# Power.net
KiCad netlist of a schematic drawn in Altium Designer
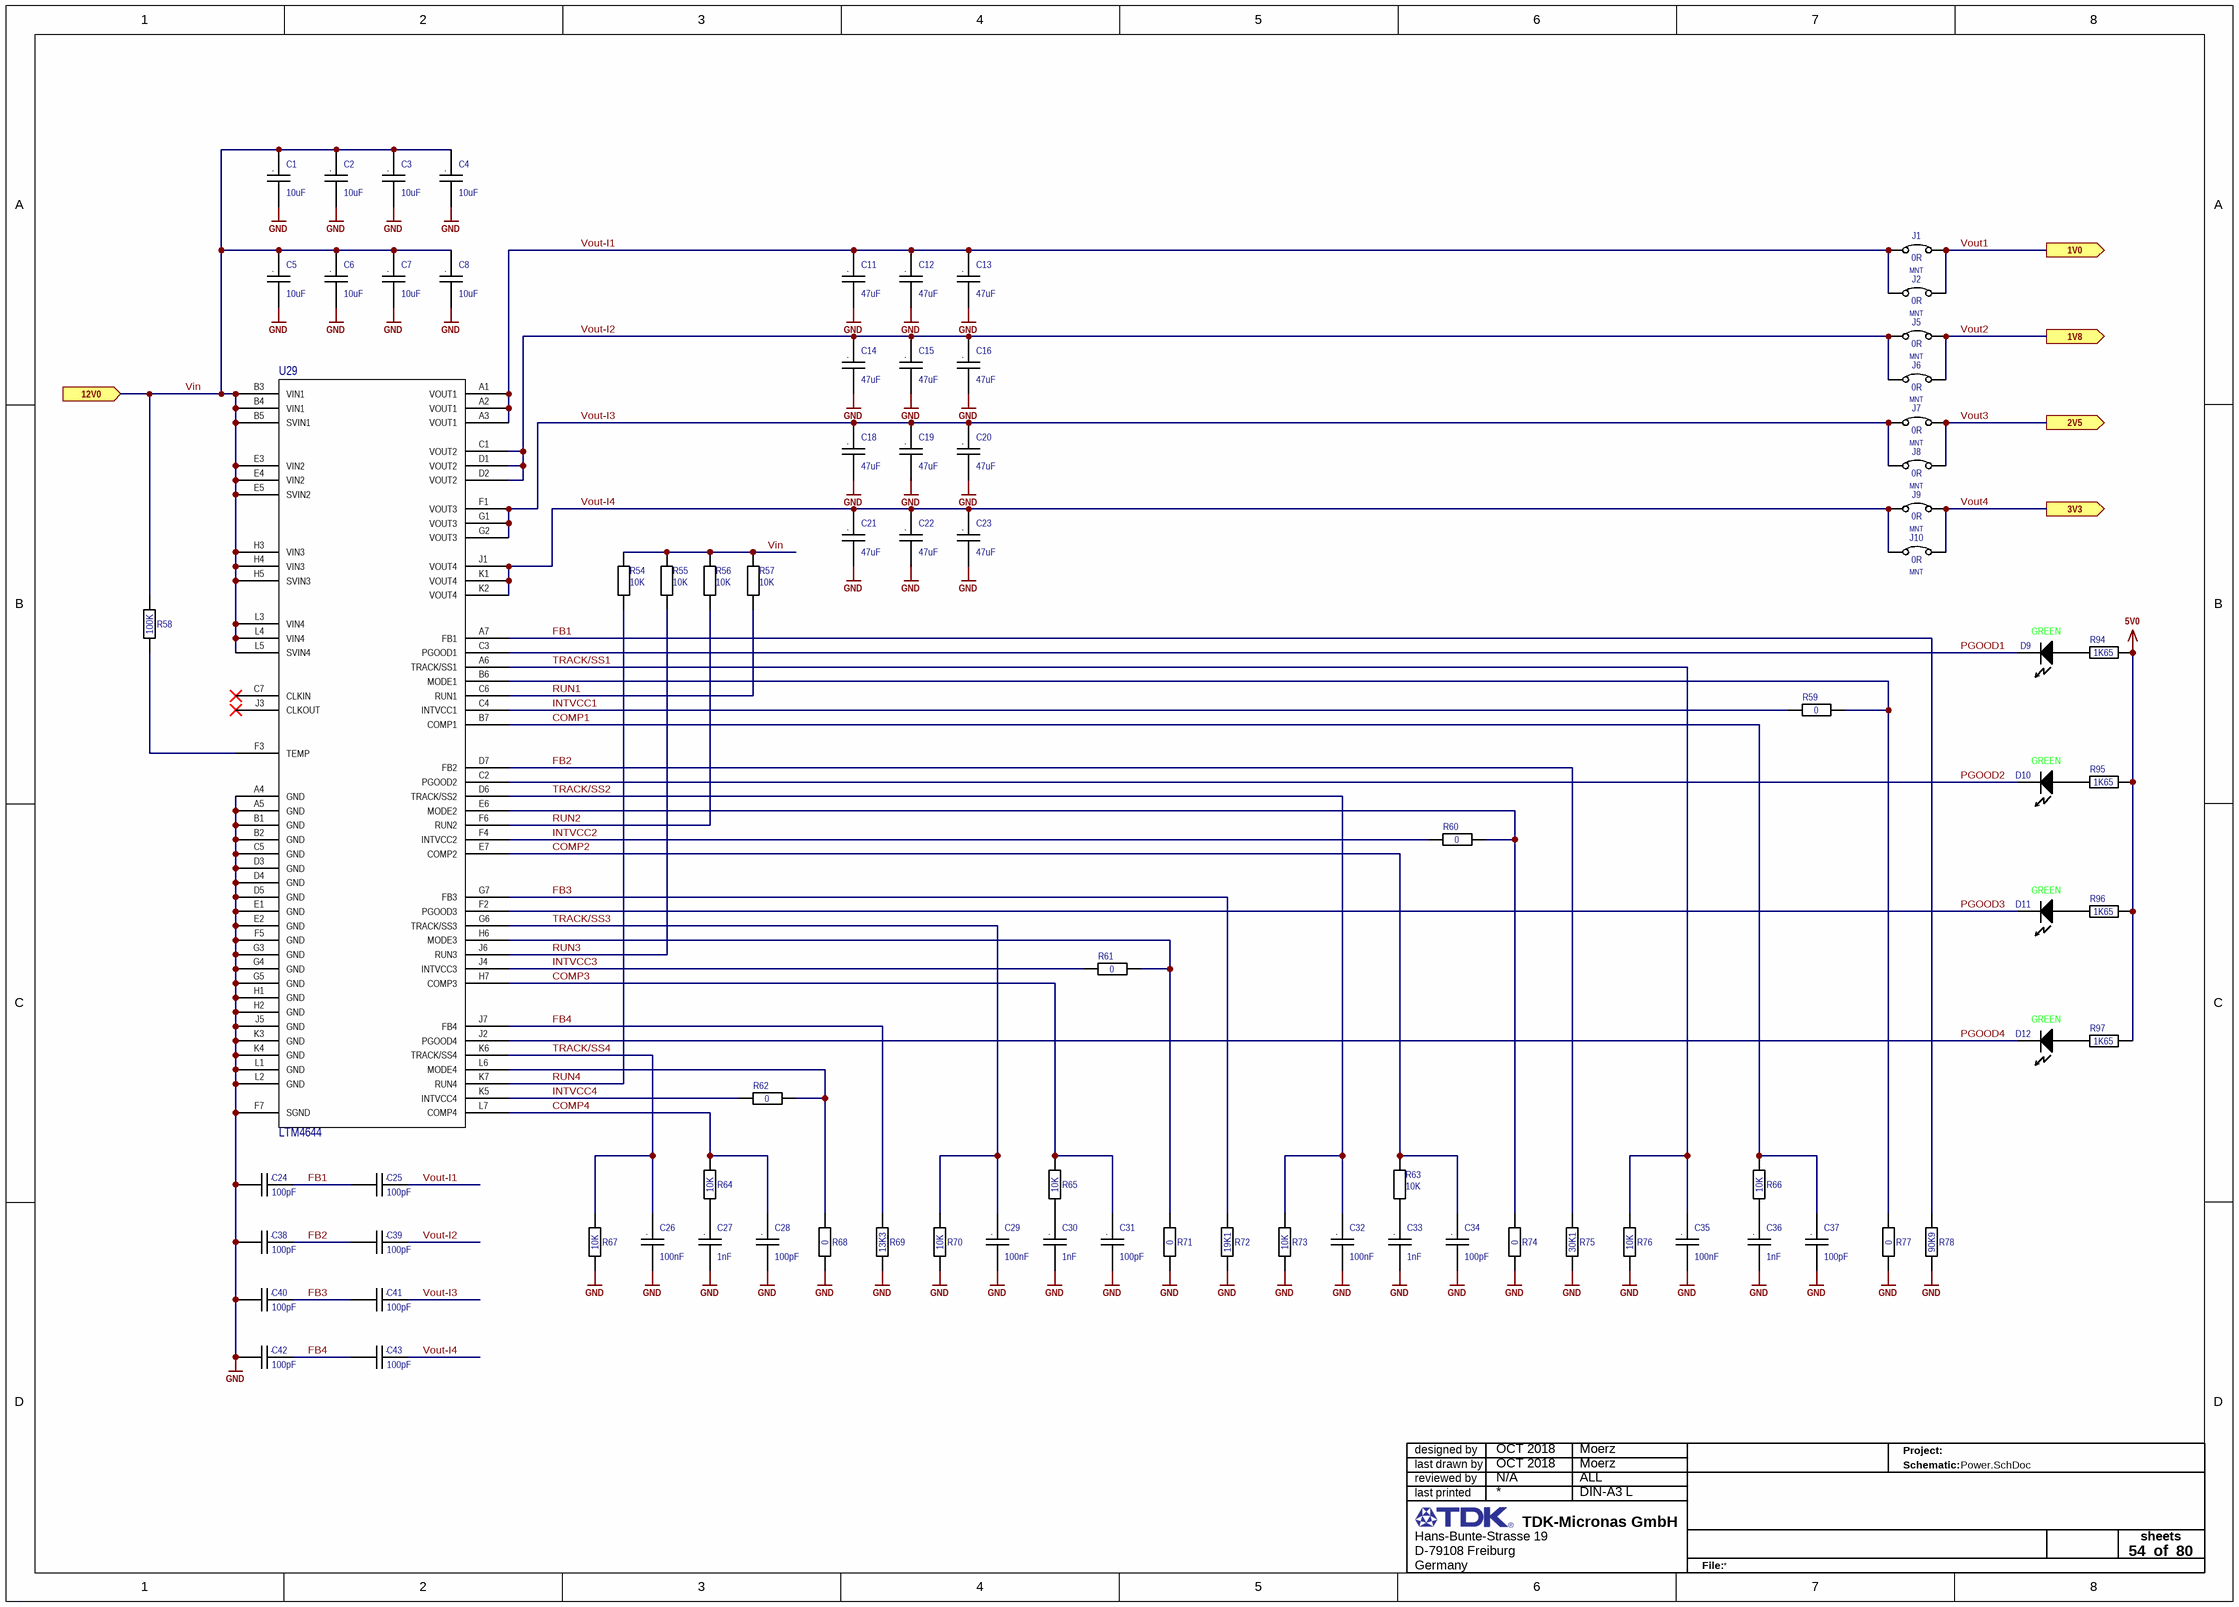
[diagram p0: Power.SchDoc]

(export (version "E")
  (design (tool "Eeschema 10.0.6"))
  (components
    (comp (ref "C1")
      (value "10uF")
      (footprint "C1206 Reflow")
      (description "CAP CER 10UF 25V X7R 1206")
      (fields
        (field (name "TOLERANCE") "±10%")
        (field (name "02. DISTRIBUTOR PART NUMBER") "445-7705-6-ND")
        (field (name "13. CREATED DATE/NAME") "AUG2018/Hören")
      )
      (libsource (lib "chickenfood") (part "C"))
    )
    (comp (ref "C2")
      (value "10uF")
      (footprint "C1206 Reflow")
      (description "CAP CER 10UF 25V X7R 1206")
      (fields
        (field (name "TOLERANCE") "±10%")
        (field (name "02. DISTRIBUTOR PART NUMBER") "445-7705-6-ND")
        (field (name "13. CREATED DATE/NAME") "AUG2018/Hören")
      )
      (libsource (lib "chickenfood") (part "C"))
    )
    (comp (ref "C3")
      (value "10uF")
      (footprint "C1206 Reflow")
      (description "CAP CER 10UF 25V X7R 1206")
      (fields
        (field (name "TOLERANCE") "±10%")
        (field (name "02. DISTRIBUTOR PART NUMBER") "445-7705-6-ND")
        (field (name "13. CREATED DATE/NAME") "AUG2018/Hören")
      )
      (libsource (lib "chickenfood") (part "C"))
    )
    (comp (ref "C4")
      (value "10uF")
      (footprint "C1206 Reflow")
      (description "CAP CER 10UF 25V X7R 1206")
      (fields
        (field (name "TOLERANCE") "±10%")
        (field (name "02. DISTRIBUTOR PART NUMBER") "445-7705-6-ND")
        (field (name "13. CREATED DATE/NAME") "AUG2018/Hören")
      )
      (libsource (lib "chickenfood") (part "C"))
    )
    (comp (ref "C5")
      (value "10uF")
      (footprint "C1206 Reflow")
      (description "CAP CER 10UF 25V X7R 1206")
      (fields
        (field (name "TOLERANCE") "±10%")
        (field (name "02. DISTRIBUTOR PART NUMBER") "445-7705-6-ND")
        (field (name "13. CREATED DATE/NAME") "AUG2018/Hören")
      )
      (libsource (lib "chickenfood") (part "C"))
    )
    (comp (ref "C6")
      (value "10uF")
      (footprint "C1206 Reflow")
      (description "CAP CER 10UF 25V X7R 1206")
      (fields
        (field (name "TOLERANCE") "±10%")
        (field (name "02. DISTRIBUTOR PART NUMBER") "445-7705-6-ND")
        (field (name "13. CREATED DATE/NAME") "AUG2018/Hören")
      )
      (libsource (lib "chickenfood") (part "C"))
    )
    (comp (ref "C7")
      (value "10uF")
      (footprint "C1206 Reflow")
      (description "CAP CER 10UF 25V X7R 1206")
      (fields
        (field (name "TOLERANCE") "±10%")
        (field (name "02. DISTRIBUTOR PART NUMBER") "445-7705-6-ND")
        (field (name "13. CREATED DATE/NAME") "AUG2018/Hören")
      )
      (libsource (lib "chickenfood") (part "C"))
    )
    (comp (ref "C8")
      (value "10uF")
      (footprint "C1206 Reflow")
      (description "CAP CER 10UF 25V X7R 1206")
      (fields
        (field (name "TOLERANCE") "±10%")
        (field (name "02. DISTRIBUTOR PART NUMBER") "445-7705-6-ND")
        (field (name "13. CREATED DATE/NAME") "AUG2018/Hören")
      )
      (libsource (lib "chickenfood") (part "C"))
    )
    (comp (ref "C11")
      (value "47uF")
      (footprint "C1210 Reflow")
      (description "CAP CER 47UF 10V X5R 1210")
      (fields
        (field (name "TOLERANCE") "±20%")
        (field (name "02. DISTRIBUTOR PART NUMBER") "1276-3380-6-ND")
        (field (name "13. CREATED DATE/NAME") "AUG2018/Hören")
      )
      (libsource (lib "chickenfood") (part "C"))
    )
    (comp (ref "C12")
      (value "47uF")
      (footprint "C1210 Reflow")
      (description "CAP CER 47UF 10V X5R 1210")
      (fields
        (field (name "TOLERANCE") "±20%")
        (field (name "02. DISTRIBUTOR PART NUMBER") "1276-3380-6-ND")
        (field (name "13. CREATED DATE/NAME") "AUG2018/Hören")
      )
      (libsource (lib "chickenfood") (part "C"))
    )
    (comp (ref "C13")
      (value "47uF")
      (footprint "C1210 Reflow")
      (description "CAP CER 47UF 10V X5R 1210")
      (fields
        (field (name "TOLERANCE") "±20%")
        (field (name "02. DISTRIBUTOR PART NUMBER") "1276-3380-6-ND")
        (field (name "13. CREATED DATE/NAME") "AUG2018/Hören")
      )
      (libsource (lib "chickenfood") (part "C"))
    )
    (comp (ref "C14")
      (value "47uF")
      (footprint "C1210 Reflow")
      (description "CAP CER 47UF 10V X5R 1210")
      (fields
        (field (name "TOLERANCE") "±20%")
        (field (name "02. DISTRIBUTOR PART NUMBER") "1276-3380-6-ND")
        (field (name "13. CREATED DATE/NAME") "AUG2018/Hören")
      )
      (libsource (lib "chickenfood") (part "C"))
    )
    (comp (ref "C15")
      (value "47uF")
      (footprint "C1210 Reflow")
      (description "CAP CER 47UF 10V X5R 1210")
      (fields
        (field (name "TOLERANCE") "±20%")
        (field (name "02. DISTRIBUTOR PART NUMBER") "1276-3380-6-ND")
        (field (name "13. CREATED DATE/NAME") "AUG2018/Hören")
      )
      (libsource (lib "chickenfood") (part "C"))
    )
    (comp (ref "C16")
      (value "47uF")
      (footprint "C1210 Reflow")
      (description "CAP CER 47UF 10V X5R 1210")
      (fields
        (field (name "TOLERANCE") "±20%")
        (field (name "02. DISTRIBUTOR PART NUMBER") "1276-3380-6-ND")
        (field (name "13. CREATED DATE/NAME") "AUG2018/Hören")
      )
      (libsource (lib "chickenfood") (part "C"))
    )
    (comp (ref "C18")
      (value "47uF")
      (footprint "C1210 Reflow")
      (description "CAP CER 47UF 10V X5R 1210")
      (fields
        (field (name "TOLERANCE") "±20%")
        (field (name "02. DISTRIBUTOR PART NUMBER") "1276-3380-6-ND")
        (field (name "13. CREATED DATE/NAME") "AUG2018/Hören")
      )
      (libsource (lib "chickenfood") (part "C"))
    )
    (comp (ref "C19")
      (value "47uF")
      (footprint "C1210 Reflow")
      (description "CAP CER 47UF 10V X5R 1210")
      (fields
        (field (name "TOLERANCE") "±20%")
        (field (name "02. DISTRIBUTOR PART NUMBER") "1276-3380-6-ND")
        (field (name "13. CREATED DATE/NAME") "AUG2018/Hören")
      )
      (libsource (lib "chickenfood") (part "C"))
    )
    (comp (ref "C20")
      (value "47uF")
      (footprint "C1210 Reflow")
      (description "CAP CER 47UF 10V X5R 1210")
      (fields
        (field (name "TOLERANCE") "±20%")
        (field (name "02. DISTRIBUTOR PART NUMBER") "1276-3380-6-ND")
        (field (name "13. CREATED DATE/NAME") "AUG2018/Hören")
      )
      (libsource (lib "chickenfood") (part "C"))
    )
    (comp (ref "C21")
      (value "47uF")
      (footprint "C1210 Reflow")
      (description "CAP CER 47UF 10V X5R 1210")
      (fields
        (field (name "TOLERANCE") "±20%")
        (field (name "02. DISTRIBUTOR PART NUMBER") "1276-3380-6-ND")
        (field (name "13. CREATED DATE/NAME") "AUG2018/Hören")
      )
      (libsource (lib "chickenfood") (part "C"))
    )
    (comp (ref "C22")
      (value "47uF")
      (footprint "C1210 Reflow")
      (description "CAP CER 47UF 10V X5R 1210")
      (fields
        (field (name "TOLERANCE") "±20%")
        (field (name "02. DISTRIBUTOR PART NUMBER") "1276-3380-6-ND")
        (field (name "13. CREATED DATE/NAME") "AUG2018/Hören")
      )
      (libsource (lib "chickenfood") (part "C"))
    )
    (comp (ref "C23")
      (value "47uF")
      (footprint "C1210 Reflow")
      (description "CAP CER 47UF 10V X5R 1210")
      (fields
        (field (name "TOLERANCE") "±20%")
        (field (name "02. DISTRIBUTOR PART NUMBER") "1276-3380-6-ND")
        (field (name "13. CREATED DATE/NAME") "AUG2018/Hören")
      )
      (libsource (lib "chickenfood") (part "C"))
    )
    (comp (ref "C24")
      (value "100pF")
      (footprint "C0402 Reflow")
      (description "CAP CER 100PF 25V C0G/NP0 0402")
      (fields
        (field (name "TOLERANCE") "±5%")
        (field (name "02. DISTRIBUTOR PART NUMBER") "399-1022-6-ND")
        (field (name "13. CREATED DATE/NAME") "AUG2018/Hören")
      )
      (libsource (lib "chickenfood") (part "C"))
    )
    (comp (ref "C25")
      (value "100pF")
      (footprint "C0402 Reflow")
      (description "CAP CER 100PF 25V C0G/NP0 0402")
      (fields
        (field (name "TOLERANCE") "±5%")
        (field (name "02. DISTRIBUTOR PART NUMBER") "399-1022-6-ND")
        (field (name "13. CREATED DATE/NAME") "AUG2018/Hören")
      )
      (libsource (lib "chickenfood") (part "C"))
    )
    (comp (ref "C26")
      (value "100nF")
      (footprint "C0402 Reflow")
      (description "CAP CER 0.1UF 25V X7R 0402")
      (fields
        (field (name "TOLERANCE") "±10%")
        (field (name "02. DISTRIBUTOR PART NUMBER") "311-2077-6-ND")
        (field (name "13. CREATED DATE/NAME") "AUG2018/Hören")
      )
      (libsource (lib "chickenfood") (part "C"))
    )
    (comp (ref "C27")
      (value "1nF")
      (footprint "C0402 Reflow")
      (description "CAP CER 1000PF 25V X7R 0402")
      (fields
        (field (name "TOLERANCE") "±10%")
        (field (name "02. DISTRIBUTOR PART NUMBER") "399-1031-6-ND")
        (field (name "13. CREATED DATE/NAME") "AUG2018/Hören")
      )
      (libsource (lib "chickenfood") (part "C"))
    )
    (comp (ref "C28")
      (value "100pF")
      (footprint "C0402 Reflow")
      (description "CAP CER 100PF 25V C0G/NP0 0402")
      (fields
        (field (name "TOLERANCE") "±5%")
        (field (name "02. DISTRIBUTOR PART NUMBER") "399-1022-6-ND")
        (field (name "13. CREATED DATE/NAME") "AUG2018/Hören")
      )
      (libsource (lib "chickenfood") (part "C"))
    )
    (comp (ref "C29")
      (value "100nF")
      (footprint "C0402 Reflow")
      (description "CAP CER 0.1UF 25V X7R 0402")
      (fields
        (field (name "TOLERANCE") "±10%")
        (field (name "02. DISTRIBUTOR PART NUMBER") "311-2077-6-ND")
        (field (name "13. CREATED DATE/NAME") "AUG2018/Hören")
      )
      (libsource (lib "chickenfood") (part "C"))
    )
    (comp (ref "C30")
      (value "1nF")
      (footprint "C0402 Reflow")
      (description "CAP CER 1000PF 25V X7R 0402")
      (fields
        (field (name "TOLERANCE") "±10%")
        (field (name "02. DISTRIBUTOR PART NUMBER") "399-1031-6-ND")
        (field (name "13. CREATED DATE/NAME") "AUG2018/Hören")
      )
      (libsource (lib "chickenfood") (part "C"))
    )
    (comp (ref "C31")
      (value "100pF")
      (footprint "C0402 Reflow")
      (description "CAP CER 100PF 25V C0G/NP0 0402")
      (fields
        (field (name "TOLERANCE") "±5%")
        (field (name "02. DISTRIBUTOR PART NUMBER") "399-1022-6-ND")
        (field (name "13. CREATED DATE/NAME") "AUG2018/Hören")
      )
      (libsource (lib "chickenfood") (part "C"))
    )
    (comp (ref "C32")
      (value "100nF")
      (footprint "C0402 Reflow")
      (description "CAP CER 0.1UF 25V X7R 0402")
      (fields
        (field (name "TOLERANCE") "±10%")
        (field (name "02. DISTRIBUTOR PART NUMBER") "311-2077-6-ND")
        (field (name "13. CREATED DATE/NAME") "AUG2018/Hören")
      )
      (libsource (lib "chickenfood") (part "C"))
    )
    (comp (ref "C33")
      (value "1nF")
      (footprint "C0402 Reflow")
      (description "CAP CER 1000PF 25V X7R 0402")
      (fields
        (field (name "TOLERANCE") "±10%")
        (field (name "02. DISTRIBUTOR PART NUMBER") "399-1031-6-ND")
        (field (name "13. CREATED DATE/NAME") "AUG2018/Hören")
      )
      (libsource (lib "chickenfood") (part "C"))
    )
    (comp (ref "C34")
      (value "100pF")
      (footprint "C0402 Reflow")
      (description "CAP CER 100PF 25V C0G/NP0 0402")
      (fields
        (field (name "TOLERANCE") "±5%")
        (field (name "02. DISTRIBUTOR PART NUMBER") "399-1022-6-ND")
        (field (name "13. CREATED DATE/NAME") "AUG2018/Hören")
      )
      (libsource (lib "chickenfood") (part "C"))
    )
    (comp (ref "C35")
      (value "100nF")
      (footprint "C0402 Reflow")
      (description "CAP CER 0.1UF 25V X7R 0402")
      (fields
        (field (name "TOLERANCE") "±10%")
        (field (name "02. DISTRIBUTOR PART NUMBER") "311-2077-6-ND")
        (field (name "13. CREATED DATE/NAME") "AUG2018/Hören")
      )
      (libsource (lib "chickenfood") (part "C"))
    )
    (comp (ref "C36")
      (value "1nF")
      (footprint "C0402 Reflow")
      (description "CAP CER 1000PF 25V X7R 0402")
      (fields
        (field (name "TOLERANCE") "±10%")
        (field (name "02. DISTRIBUTOR PART NUMBER") "399-1031-6-ND")
        (field (name "13. CREATED DATE/NAME") "AUG2018/Hören")
      )
      (libsource (lib "chickenfood") (part "C"))
    )
    (comp (ref "C37")
      (value "100pF")
      (footprint "C0402 Reflow")
      (description "CAP CER 100PF 25V C0G/NP0 0402")
      (fields
        (field (name "TOLERANCE") "±5%")
        (field (name "02. DISTRIBUTOR PART NUMBER") "399-1022-6-ND")
        (field (name "13. CREATED DATE/NAME") "AUG2018/Hören")
      )
      (libsource (lib "chickenfood") (part "C"))
    )
    (comp (ref "C38")
      (value "100pF")
      (footprint "C0402 Reflow")
      (description "CAP CER 100PF 25V C0G/NP0 0402")
      (fields
        (field (name "TOLERANCE") "±5%")
        (field (name "02. DISTRIBUTOR PART NUMBER") "399-1022-6-ND")
        (field (name "13. CREATED DATE/NAME") "AUG2018/Hören")
      )
      (libsource (lib "chickenfood") (part "C"))
    )
    (comp (ref "C39")
      (value "100pF")
      (footprint "C0402 Reflow")
      (description "CAP CER 100PF 25V C0G/NP0 0402")
      (fields
        (field (name "TOLERANCE") "±5%")
        (field (name "02. DISTRIBUTOR PART NUMBER") "399-1022-6-ND")
        (field (name "13. CREATED DATE/NAME") "AUG2018/Hören")
      )
      (libsource (lib "chickenfood") (part "C"))
    )
    (comp (ref "C40")
      (value "100pF")
      (footprint "C0402 Reflow")
      (description "CAP CER 100PF 25V C0G/NP0 0402")
      (fields
        (field (name "TOLERANCE") "±5%")
        (field (name "02. DISTRIBUTOR PART NUMBER") "399-1022-6-ND")
        (field (name "13. CREATED DATE/NAME") "AUG2018/Hören")
      )
      (libsource (lib "chickenfood") (part "C"))
    )
    (comp (ref "C41")
      (value "100pF")
      (footprint "C0402 Reflow")
      (description "CAP CER 100PF 25V C0G/NP0 0402")
      (fields
        (field (name "TOLERANCE") "±5%")
        (field (name "02. DISTRIBUTOR PART NUMBER") "399-1022-6-ND")
        (field (name "13. CREATED DATE/NAME") "AUG2018/Hören")
      )
      (libsource (lib "chickenfood") (part "C"))
    )
    (comp (ref "C42")
      (value "100pF")
      (footprint "C0402 Reflow")
      (description "CAP CER 100PF 25V C0G/NP0 0402")
      (fields
        (field (name "TOLERANCE") "±5%")
        (field (name "02. DISTRIBUTOR PART NUMBER") "399-1022-6-ND")
        (field (name "13. CREATED DATE/NAME") "AUG2018/Hören")
      )
      (libsource (lib "chickenfood") (part "C"))
    )
    (comp (ref "C43")
      (value "100pF")
      (footprint "C0402 Reflow")
      (description "CAP CER 100PF 25V C0G/NP0 0402")
      (fields
        (field (name "TOLERANCE") "±5%")
        (field (name "02. DISTRIBUTOR PART NUMBER") "399-1022-6-ND")
        (field (name "13. CREATED DATE/NAME") "AUG2018/Hören")
      )
      (libsource (lib "chickenfood") (part "C"))
    )
    (comp (ref "D9")
      (value "D")
      (footprint "L0603G")
      (description "LED GREEN DIFFUSED 0603 SMD")
      (fields
        (field (name "02. DISTRIBUTOR PART NUMBER") "475-2709-6-ND")
        (field (name "07. MANUFACTURER  PART NUMBER") "LG L29K-G2J1-24-Z")
        (field (name "COLOR") "GREEN")
        (field (name "13. CREATED DATE/NAME") "AUG2018/Hören")
      )
      (libsource (lib "chickenfood") (part "LED"))
    )
    (comp (ref "D10")
      (value "D")
      (footprint "L0603G")
      (description "LED GREEN DIFFUSED 0603 SMD")
      (fields
        (field (name "02. DISTRIBUTOR PART NUMBER") "475-2709-6-ND")
        (field (name "07. MANUFACTURER  PART NUMBER") "LG L29K-G2J1-24-Z")
        (field (name "COLOR") "GREEN")
        (field (name "13. CREATED DATE/NAME") "AUG2018/Hören")
      )
      (libsource (lib "chickenfood") (part "LED"))
    )
    (comp (ref "D11")
      (value "D")
      (footprint "L0603G")
      (description "LED GREEN DIFFUSED 0603 SMD")
      (fields
        (field (name "02. DISTRIBUTOR PART NUMBER") "475-2709-6-ND")
        (field (name "07. MANUFACTURER  PART NUMBER") "LG L29K-G2J1-24-Z")
        (field (name "COLOR") "GREEN")
        (field (name "13. CREATED DATE/NAME") "AUG2018/Hören")
      )
      (libsource (lib "chickenfood") (part "LED"))
    )
    (comp (ref "D12")
      (value "D")
      (footprint "L0603G")
      (description "LED GREEN DIFFUSED 0603 SMD")
      (fields
        (field (name "02. DISTRIBUTOR PART NUMBER") "475-2709-6-ND")
        (field (name "07. MANUFACTURER  PART NUMBER") "LG L29K-G2J1-24-Z")
        (field (name "COLOR") "GREEN")
        (field (name "13. CREATED DATE/NAME") "AUG2018/Hören")
      )
      (libsource (lib "chickenfood") (part "LED"))
    )
    (comp (ref "J1")
      (value "0R")
      (footprint "JumperSMD")
      (description "RES SMD 0 OHM JUMPER 1/10W 0603")
      (fields
        (field (name "02. DISTRIBUTOR PART NUMBER") "311-0.0GRDKR-ND")
        (field (name "07. MANUFACTURER  PART NUMBER") "RC0603JR-070RL")
        (field (name "POPULATED") "MNT")
      )
      (libsource (lib "chickenfood") (part "Jumper SMD"))
    )
    (comp (ref "J2")
      (value "0R")
      (footprint "JumperSMD")
      (description "RES SMD 0 OHM JUMPER 1/10W 0603")
      (fields
        (field (name "02. DISTRIBUTOR PART NUMBER") "311-0.0GRDKR-ND")
        (field (name "07. MANUFACTURER  PART NUMBER") "RC0603JR-070RL")
        (field (name "POPULATED") "MNT")
      )
      (libsource (lib "chickenfood") (part "Jumper SMD"))
    )
    (comp (ref "J5")
      (value "0R")
      (footprint "JumperSMD")
      (description "RES SMD 0 OHM JUMPER 1/10W 0603")
      (fields
        (field (name "02. DISTRIBUTOR PART NUMBER") "311-0.0GRDKR-ND")
        (field (name "07. MANUFACTURER  PART NUMBER") "RC0603JR-070RL")
        (field (name "POPULATED") "MNT")
      )
      (libsource (lib "chickenfood") (part "Jumper SMD"))
    )
    (comp (ref "J6")
      (value "0R")
      (footprint "JumperSMD")
      (description "RES SMD 0 OHM JUMPER 1/10W 0603")
      (fields
        (field (name "02. DISTRIBUTOR PART NUMBER") "311-0.0GRDKR-ND")
        (field (name "07. MANUFACTURER  PART NUMBER") "RC0603JR-070RL")
        (field (name "POPULATED") "MNT")
      )
      (libsource (lib "chickenfood") (part "Jumper SMD"))
    )
    (comp (ref "J7")
      (value "0R")
      (footprint "JumperSMD")
      (description "RES SMD 0 OHM JUMPER 1/10W 0603")
      (fields
        (field (name "02. DISTRIBUTOR PART NUMBER") "311-0.0GRDKR-ND")
        (field (name "07. MANUFACTURER  PART NUMBER") "RC0603JR-070RL")
        (field (name "POPULATED") "MNT")
      )
      (libsource (lib "chickenfood") (part "Jumper SMD"))
    )
    (comp (ref "J8")
      (value "0R")
      (footprint "JumperSMD")
      (description "RES SMD 0 OHM JUMPER 1/10W 0603")
      (fields
        (field (name "02. DISTRIBUTOR PART NUMBER") "311-0.0GRDKR-ND")
        (field (name "07. MANUFACTURER  PART NUMBER") "RC0603JR-070RL")
        (field (name "POPULATED") "MNT")
      )
      (libsource (lib "chickenfood") (part "Jumper SMD"))
    )
    (comp (ref "J9")
      (value "0R")
      (footprint "JumperSMD")
      (description "RES SMD 0 OHM JUMPER 1/10W 0603")
      (fields
        (field (name "02. DISTRIBUTOR PART NUMBER") "311-0.0GRDKR-ND")
        (field (name "07. MANUFACTURER  PART NUMBER") "RC0603JR-070RL")
        (field (name "POPULATED") "MNT")
      )
      (libsource (lib "chickenfood") (part "Jumper SMD"))
    )
    (comp (ref "J10")
      (value "0R")
      (footprint "JumperSMD")
      (description "RES SMD 0 OHM JUMPER 1/10W 0603")
      (fields
        (field (name "02. DISTRIBUTOR PART NUMBER") "311-0.0GRDKR-ND")
        (field (name "07. MANUFACTURER  PART NUMBER") "RC0603JR-070RL")
        (field (name "POPULATED") "MNT")
      )
      (libsource (lib "chickenfood") (part "Jumper SMD"))
    )
    (comp (ref "R54")
      (value "10K")
      (footprint "R0402 Reflow")
      (description "RES SMD 10K OHM 1% 1/16W 0402")
      (fields
        (field (name "TOLERANCE") "±1%")
        (field (name "02. DISTRIBUTOR PART NUMBER") "311-10.0KLRDKR-ND")
        (field (name "13. CREATED DATE/NAME") "AUG2018/Hören")
      )
      (libsource (lib "chickenfood") (part "R"))
    )
    (comp (ref "R55")
      (value "10K")
      (footprint "R0402 Reflow")
      (description "RES SMD 10K OHM 1% 1/16W 0402")
      (fields
        (field (name "TOLERANCE") "±1%")
        (field (name "02. DISTRIBUTOR PART NUMBER") "311-10.0KLRDKR-ND")
        (field (name "13. CREATED DATE/NAME") "AUG2018/Hören")
      )
      (libsource (lib "chickenfood") (part "R"))
    )
    (comp (ref "R56")
      (value "10K")
      (footprint "R0402 Reflow")
      (description "RES SMD 10K OHM 1% 1/16W 0402")
      (fields
        (field (name "TOLERANCE") "±1%")
        (field (name "02. DISTRIBUTOR PART NUMBER") "311-10.0KLRDKR-ND")
        (field (name "13. CREATED DATE/NAME") "AUG2018/Hören")
      )
      (libsource (lib "chickenfood") (part "R"))
    )
    (comp (ref "R57")
      (value "10K")
      (footprint "R0402 Reflow")
      (description "RES SMD 10K OHM 1% 1/16W 0402")
      (fields
        (field (name "TOLERANCE") "±1%")
        (field (name "02. DISTRIBUTOR PART NUMBER") "311-10.0KLRDKR-ND")
        (field (name "13. CREATED DATE/NAME") "AUG2018/Hören")
      )
      (libsource (lib "chickenfood") (part "R"))
    )
    (comp (ref "R58")
      (value "100K")
      (footprint "R0402 Reflow")
      (description "RES SMD 100K OHM 1% 1/16W 0402")
      (fields
        (field (name "TOLERANCE") "±1%")
        (field (name "02. DISTRIBUTOR PART NUMBER") "311-100KLRDKR-ND")
        (field (name "13. CREATED DATE/NAME") "AUG2018/Hören")
      )
      (libsource (lib "chickenfood") (part "R"))
    )
    (comp (ref "R59")
      (value "0")
      (footprint "R0402 Reflow")
      (description "RES SMD 0 OHM JUMPER 1/16W 0402")
      (fields
        (field (name "02. DISTRIBUTOR PART NUMBER") "311-0.0JRDKR-ND")
        (field (name "07. MANUFACTURER  PART NUMBER") "RC0402JR-070RL")
        (field (name "13. CREATED DATE/NAME") "AUG2018/Hören")
      )
      (libsource (lib "") (part "R_1"))
    )
    (comp (ref "R60")
      (value "0")
      (footprint "R0402 Reflow")
      (description "RES SMD 0 OHM JUMPER 1/16W 0402")
      (fields
        (field (name "02. DISTRIBUTOR PART NUMBER") "311-0.0JRDKR-ND")
        (field (name "07. MANUFACTURER  PART NUMBER") "RC0402JR-070RL")
        (field (name "13. CREATED DATE/NAME") "AUG2018/Hören")
      )
      (libsource (lib "") (part "R_1"))
    )
    (comp (ref "R61")
      (value "0")
      (footprint "R0402 Reflow")
      (description "RES SMD 0 OHM JUMPER 1/16W 0402")
      (fields
        (field (name "02. DISTRIBUTOR PART NUMBER") "311-0.0JRDKR-ND")
        (field (name "07. MANUFACTURER  PART NUMBER") "RC0402JR-070RL")
        (field (name "13. CREATED DATE/NAME") "AUG2018/Hören")
      )
      (libsource (lib "") (part "R_1"))
    )
    (comp (ref "R62")
      (value "0")
      (footprint "R0402 Reflow")
      (description "RES SMD 0 OHM JUMPER 1/16W 0402")
      (fields
        (field (name "02. DISTRIBUTOR PART NUMBER") "311-0.0JRDKR-ND")
        (field (name "07. MANUFACTURER  PART NUMBER") "RC0402JR-070RL")
        (field (name "13. CREATED DATE/NAME") "AUG2018/Hören")
      )
      (libsource (lib "") (part "R_1"))
    )
    (comp (ref "R63")
      (value "10K")
      (footprint "R0402 Reflow")
      (description "RES SMD 10K OHM 1% 1/16W 0402")
      (fields
        (field (name "TOLERANCE") "±1%")
        (field (name "02. DISTRIBUTOR PART NUMBER") "311-10.0KLRDKR-ND")
        (field (name "13. CREATED DATE/NAME") "AUG2018/Hören")
      )
      (libsource (lib "chickenfood") (part "R"))
    )
    (comp (ref "R64")
      (value "10K")
      (footprint "R0402 Reflow")
      (description "RES SMD 10K OHM 1% 1/16W 0402")
      (fields
        (field (name "TOLERANCE") "±1%")
        (field (name "02. DISTRIBUTOR PART NUMBER") "311-10.0KLRDKR-ND")
        (field (name "13. CREATED DATE/NAME") "AUG2018/Hören")
      )
      (libsource (lib "chickenfood") (part "R"))
    )
    (comp (ref "R65")
      (value "10K")
      (footprint "R0402 Reflow")
      (description "RES SMD 10K OHM 1% 1/16W 0402")
      (fields
        (field (name "TOLERANCE") "±1%")
        (field (name "02. DISTRIBUTOR PART NUMBER") "311-10.0KLRDKR-ND")
        (field (name "13. CREATED DATE/NAME") "AUG2018/Hören")
      )
      (libsource (lib "chickenfood") (part "R"))
    )
    (comp (ref "R66")
      (value "10K")
      (footprint "R0402 Reflow")
      (description "RES SMD 10K OHM 1% 1/16W 0402")
      (fields
        (field (name "TOLERANCE") "±1%")
        (field (name "02. DISTRIBUTOR PART NUMBER") "311-10.0KLRDKR-ND")
        (field (name "13. CREATED DATE/NAME") "AUG2018/Hören")
      )
      (libsource (lib "chickenfood") (part "R"))
    )
    (comp (ref "R67")
      (value "10K")
      (footprint "R0402 Reflow")
      (description "RES SMD 10K OHM 1% 1/16W 0402")
      (fields
        (field (name "TOLERANCE") "±1%")
        (field (name "02. DISTRIBUTOR PART NUMBER") "311-10.0KLRDKR-ND")
        (field (name "13. CREATED DATE/NAME") "AUG2018/Hören")
      )
      (libsource (lib "chickenfood") (part "R"))
    )
    (comp (ref "R68")
      (value "0")
      (footprint "R0402 Reflow")
      (description "RES SMD 0 OHM JUMPER 1/16W 0402")
      (fields
        (field (name "02. DISTRIBUTOR PART NUMBER") "311-0.0JRDKR-ND")
        (field (name "07. MANUFACTURER  PART NUMBER") "RC0402JR-070RL")
        (field (name "13. CREATED DATE/NAME") "AUG2018/Hören")
      )
      (libsource (lib "chickenfood") (part "R"))
    )
    (comp (ref "R69")
      (value "13K3")
      (footprint "R0402 Reflow")
      (description "RES SMD 13.3K OHM 1% 1/16W 0402")
      (fields
        (field (name "TOLERANCE") "±1%")
        (field (name "02. DISTRIBUTOR PART NUMBER") "YAG2974DKR-ND")
        (field (name "13. CREATED DATE/NAME") "AUG2018/Hören")
      )
      (libsource (lib "chickenfood") (part "R"))
    )
    (comp (ref "R70")
      (value "10K")
      (footprint "R0402 Reflow")
      (description "RES SMD 10K OHM 1% 1/16W 0402")
      (fields
        (field (name "TOLERANCE") "±1%")
        (field (name "02. DISTRIBUTOR PART NUMBER") "311-10.0KLRDKR-ND")
        (field (name "13. CREATED DATE/NAME") "AUG2018/Hören")
      )
      (libsource (lib "chickenfood") (part "R"))
    )
    (comp (ref "R71")
      (value "0")
      (footprint "R0402 Reflow")
      (description "RES SMD 0 OHM JUMPER 1/16W 0402")
      (fields
        (field (name "02. DISTRIBUTOR PART NUMBER") "311-0.0JRDKR-ND")
        (field (name "07. MANUFACTURER  PART NUMBER") "RC0402JR-070RL")
        (field (name "13. CREATED DATE/NAME") "AUG2018/Hören")
      )
      (libsource (lib "chickenfood") (part "R"))
    )
    (comp (ref "R72")
      (value "19K1")
      (footprint "R0402 Reflow")
      (description "RES SMD 19.1K OHM 1% 1/16W 0402")
      (fields
        (field (name "TOLERANCE") "±1%")
        (field (name "02. DISTRIBUTOR PART NUMBER") "311-19.1KLRDKR-ND")
        (field (name "13. CREATED DATE/NAME") "AUG2018/Hören")
      )
      (libsource (lib "chickenfood") (part "R"))
    )
    (comp (ref "R73")
      (value "10K")
      (footprint "R0402 Reflow")
      (description "RES SMD 10K OHM 1% 1/16W 0402")
      (fields
        (field (name "TOLERANCE") "±1%")
        (field (name "02. DISTRIBUTOR PART NUMBER") "311-10.0KLRDKR-ND")
        (field (name "13. CREATED DATE/NAME") "AUG2018/Hören")
      )
      (libsource (lib "chickenfood") (part "R"))
    )
    (comp (ref "R74")
      (value "0")
      (footprint "R0402 Reflow")
      (description "RES SMD 0 OHM JUMPER 1/16W 0402")
      (fields
        (field (name "02. DISTRIBUTOR PART NUMBER") "311-0.0JRDKR-ND")
        (field (name "07. MANUFACTURER  PART NUMBER") "RC0402JR-070RL")
        (field (name "13. CREATED DATE/NAME") "AUG2018/Hören")
      )
      (libsource (lib "chickenfood") (part "R"))
    )
    (comp (ref "R75")
      (value "30K1")
      (footprint "R0402 Reflow")
      (description "RES SMD 30.1K OHM 1% 1/16W 0402")
      (fields
        (field (name "TOLERANCE") "±1%")
        (field (name "02. DISTRIBUTOR PART NUMBER") "311-30.1KLRDKR-ND")
        (field (name "13. CREATED DATE/NAME") "AUG2018/Hören")
      )
      (libsource (lib "chickenfood") (part "R"))
    )
    (comp (ref "R76")
      (value "10K")
      (footprint "R0402 Reflow")
      (description "RES SMD 10K OHM 1% 1/16W 0402")
      (fields
        (field (name "TOLERANCE") "±1%")
        (field (name "02. DISTRIBUTOR PART NUMBER") "311-10.0KLRDKR-ND")
        (field (name "13. CREATED DATE/NAME") "AUG2018/Hören")
      )
      (libsource (lib "chickenfood") (part "R"))
    )
    (comp (ref "R77")
      (value "0")
      (footprint "R0402 Reflow")
      (description "RES SMD 0 OHM JUMPER 1/16W 0402")
      (fields
        (field (name "02. DISTRIBUTOR PART NUMBER") "311-0.0JRDKR-ND")
        (field (name "07. MANUFACTURER  PART NUMBER") "RC0402JR-070RL")
        (field (name "13. CREATED DATE/NAME") "AUG2018/Hören")
      )
      (libsource (lib "chickenfood") (part "R"))
    )
    (comp (ref "R78")
      (value "90K9")
      (footprint "R0402 Reflow")
      (description "RES SMD 90.9K OHM 1% 1/16W 0402")
      (fields
        (field (name "TOLERANCE") "±1%")
        (field (name "02. DISTRIBUTOR PART NUMBER") "311-90.9KLRDKR-ND")
        (field (name "13. CREATED DATE/NAME") "AUG2018/Hören")
      )
      (libsource (lib "chickenfood") (part "R"))
    )
    (comp (ref "R94")
      (value "1K65")
      (footprint "R0402 Reflow")
      (description "RES SMD 1.65K OHM 1% 1/16W 0402")
      (fields
        (field (name "TOLERANCE") "±1%")
        (field (name "02. DISTRIBUTOR PART NUMBER") "YAG3043DKR-ND")
        (field (name "13. CREATED DATE/NAME") "AUG2018/Hören")
      )
      (libsource (lib "") (part "R_2"))
    )
    (comp (ref "R95")
      (value "1K65")
      (footprint "R0402 Reflow")
      (description "RES SMD 1.65K OHM 1% 1/16W 0402")
      (fields
        (field (name "TOLERANCE") "±1%")
        (field (name "02. DISTRIBUTOR PART NUMBER") "YAG3043DKR-ND")
        (field (name "13. CREATED DATE/NAME") "AUG2018/Hören")
      )
      (libsource (lib "") (part "R_2"))
    )
    (comp (ref "R96")
      (value "1K65")
      (footprint "R0402 Reflow")
      (description "RES SMD 1.65K OHM 1% 1/16W 0402")
      (fields
        (field (name "TOLERANCE") "±1%")
        (field (name "02. DISTRIBUTOR PART NUMBER") "YAG3043DKR-ND")
        (field (name "13. CREATED DATE/NAME") "AUG2018/Hören")
      )
      (libsource (lib "") (part "R_2"))
    )
    (comp (ref "R97")
      (value "1K65")
      (footprint "R0402 Reflow")
      (description "RES SMD 1.65K OHM 1% 1/16W 0402")
      (fields
        (field (name "TOLERANCE") "±1%")
        (field (name "02. DISTRIBUTOR PART NUMBER") "YAG3043DKR-ND")
        (field (name "13. CREATED DATE/NAME") "AUG2018/Hören")
      )
      (libsource (lib "") (part "R_2"))
    )
    (comp (ref "U29")
      (value "U")
      (footprint "LTM4644")
      (description "DC DC CONVERTER 4X0.6-5.5V")
      (fields
        (field (name "MFR") "LINEAR TECHNOLOGY")
        (field (name "02. DISTRIBUTOR PART NUMBER") "LTM4644EY#PBF-ND")
        (field (name "NICNAME") "LTM4644")
      )
      (libsource (lib "tom") (part "LTM4644"))
    )
  )
  (nets
    (net (code "1") (name "/COMP1") (class "Default")
      (node (ref "C37") (pin "1") (pinfunction "1_1") (pintype "passive"))
      (node (ref "R66") (pin "2") (pinfunction "2_2") (pintype "passive"))
      (node (ref "U29") (pin "B7") (pinfunction "COMP1_B7") (pintype "passive"))
    )
    (net (code "2") (name "/COMP2") (class "Default")
      (node (ref "C34") (pin "1") (pinfunction "1_1") (pintype "passive"))
      (node (ref "R63") (pin "2") (pinfunction "2_2") (pintype "passive"))
      (node (ref "U29") (pin "E7") (pinfunction "COMP2_E7") (pintype "passive"))
    )
    (net (code "3") (name "/COMP3") (class "Default")
      (node (ref "C31") (pin "1") (pinfunction "1_1") (pintype "passive"))
      (node (ref "R65") (pin "2") (pinfunction "2_2") (pintype "passive"))
      (node (ref "U29") (pin "H7") (pinfunction "COMP3_H7") (pintype "passive"))
    )
    (net (code "4") (name "/COMP4") (class "Default")
      (node (ref "C28") (pin "1") (pinfunction "1_1") (pintype "passive"))
      (node (ref "R64") (pin "2") (pinfunction "2_2") (pintype "passive"))
      (node (ref "U29") (pin "L7") (pinfunction "COMP4_L7") (pintype "passive"))
    )
    (net (code "5") (name "/FB1") (class "Default")
      (node (ref "C24") (pin "1") (pinfunction "1_1") (pintype "passive"))
      (node (ref "C25") (pin "2") (pinfunction "2_2") (pintype "passive"))
      (node (ref "R78") (pin "2") (pinfunction "2_2") (pintype "passive"))
      (node (ref "U29") (pin "A7") (pinfunction "FB1_A7") (pintype "passive"))
    )
    (net (code "6") (name "/FB2") (class "Default")
      (node (ref "C38") (pin "1") (pinfunction "1_1") (pintype "passive"))
      (node (ref "C39") (pin "2") (pinfunction "2_2") (pintype "passive"))
      (node (ref "R75") (pin "2") (pinfunction "2_2") (pintype "passive"))
      (node (ref "U29") (pin "D7") (pinfunction "FB2_D7") (pintype "passive"))
    )
    (net (code "7") (name "/FB3") (class "Default")
      (node (ref "C40") (pin "1") (pinfunction "1_1") (pintype "passive"))
      (node (ref "C41") (pin "2") (pinfunction "2_2") (pintype "passive"))
      (node (ref "R72") (pin "2") (pinfunction "2_2") (pintype "passive"))
      (node (ref "U29") (pin "G7") (pinfunction "FB3_G7") (pintype "passive"))
    )
    (net (code "8") (name "/FB4") (class "Default")
      (node (ref "C42") (pin "1") (pinfunction "1_1") (pintype "passive"))
      (node (ref "C43") (pin "2") (pinfunction "2_2") (pintype "passive"))
      (node (ref "R69") (pin "2") (pinfunction "2_2") (pintype "passive"))
      (node (ref "U29") (pin "J7") (pinfunction "FB4_J7") (pintype "passive"))
    )
    (net (code "9") (name "/INTVCC1") (class "Default")
      (node (ref "R59") (pin "2") (pinfunction "2_2") (pintype "passive"))
      (node (ref "U29") (pin "C4") (pinfunction "INTVCC1_C4") (pintype "passive"))
    )
    (net (code "10") (name "/INTVCC2") (class "Default")
      (node (ref "R60") (pin "2") (pinfunction "2_2") (pintype "passive"))
      (node (ref "U29") (pin "F4") (pinfunction "INTVCC2_F4") (pintype "passive"))
    )
    (net (code "11") (name "/INTVCC3") (class "Default")
      (node (ref "R61") (pin "2") (pinfunction "2_2") (pintype "passive"))
      (node (ref "U29") (pin "J4") (pinfunction "INTVCC3_J4") (pintype "passive"))
    )
    (net (code "12") (name "/INTVCC4") (class "Default")
      (node (ref "R62") (pin "2") (pinfunction "2_2") (pintype "passive"))
      (node (ref "U29") (pin "K5") (pinfunction "INTVCC4_K5") (pintype "passive"))
    )
    (net (code "13") (name "/PGOOD1") (class "Default")
      (node (ref "D9") (pin "2") (pinfunction "Cathode_2") (pintype "passive"))
      (node (ref "U29") (pin "C3") (pinfunction "PGOOD1_C3") (pintype "passive"))
    )
    (net (code "14") (name "/PGOOD2") (class "Default")
      (node (ref "D10") (pin "2") (pinfunction "Cathode_2") (pintype "passive"))
      (node (ref "U29") (pin "C2") (pinfunction "PGOOD2_C2") (pintype "passive"))
    )
    (net (code "15") (name "/PGOOD3") (class "Default")
      (node (ref "D11") (pin "2") (pinfunction "Cathode_2") (pintype "passive"))
      (node (ref "U29") (pin "F2") (pinfunction "PGOOD3_F2") (pintype "passive"))
    )
    (net (code "16") (name "/PGOOD4") (class "Default")
      (node (ref "D12") (pin "2") (pinfunction "Cathode_2") (pintype "passive"))
      (node (ref "U29") (pin "J2") (pinfunction "PGOOD4_J2") (pintype "passive"))
    )
    (net (code "17") (name "/RUN1") (class "Default")
      (node (ref "R57") (pin "1") (pinfunction "1_1") (pintype "passive"))
      (node (ref "U29") (pin "C6") (pinfunction "RUN1_C6") (pintype "passive"))
    )
    (net (code "18") (name "/RUN2") (class "Default")
      (node (ref "R56") (pin "1") (pinfunction "1_1") (pintype "passive"))
      (node (ref "U29") (pin "F6") (pinfunction "RUN2_F6") (pintype "passive"))
    )
    (net (code "19") (name "/RUN3") (class "Default")
      (node (ref "R55") (pin "1") (pinfunction "1_1") (pintype "passive"))
      (node (ref "U29") (pin "J6") (pinfunction "RUN3_J6") (pintype "passive"))
    )
    (net (code "20") (name "/RUN4") (class "Default")
      (node (ref "R54") (pin "1") (pinfunction "1_1") (pintype "passive"))
      (node (ref "U29") (pin "K7") (pinfunction "RUN4_K7") (pintype "passive"))
    )
    (net (code "21") (name "/TRACK{slash}SS1") (class "Default")
      (node (ref "C35") (pin "1") (pinfunction "1_1") (pintype "passive"))
      (node (ref "R76") (pin "2") (pinfunction "2_2") (pintype "passive"))
      (node (ref "U29") (pin "A6") (pinfunction "TRACK/SS1_A6") (pintype "passive"))
    )
    (net (code "22") (name "/TRACK{slash}SS2") (class "Default")
      (node (ref "C32") (pin "1") (pinfunction "1_1") (pintype "passive"))
      (node (ref "R73") (pin "2") (pinfunction "2_2") (pintype "passive"))
      (node (ref "U29") (pin "D6") (pinfunction "TRACK/SS2_D6") (pintype "passive"))
    )
    (net (code "23") (name "/TRACK{slash}SS3") (class "Default")
      (node (ref "C29") (pin "1") (pinfunction "1_1") (pintype "passive"))
      (node (ref "R70") (pin "2") (pinfunction "2_2") (pintype "passive"))
      (node (ref "U29") (pin "G6") (pinfunction "TRACK/SS3_G6") (pintype "passive"))
    )
    (net (code "24") (name "/TRACK{slash}SS4") (class "Default")
      (node (ref "C26") (pin "1") (pinfunction "1_1") (pintype "passive"))
      (node (ref "R67") (pin "2") (pinfunction "2_2") (pintype "passive"))
      (node (ref "U29") (pin "K6") (pinfunction "TRACK/SS4_K6") (pintype "passive"))
    )
    (net (code "25") (name "/Vin") (class "Default")
      (node (ref "C1") (pin "1") (pinfunction "1_1") (pintype "passive"))
      (node (ref "C2") (pin "1") (pinfunction "1_1") (pintype "passive"))
      (node (ref "C3") (pin "1") (pinfunction "1_1") (pintype "passive"))
      (node (ref "C4") (pin "1") (pinfunction "1_1") (pintype "passive"))
      (node (ref "C5") (pin "1") (pinfunction "1_1") (pintype "passive"))
      (node (ref "C6") (pin "1") (pinfunction "1_1") (pintype "passive"))
      (node (ref "C7") (pin "1") (pinfunction "1_1") (pintype "passive"))
      (node (ref "C8") (pin "1") (pinfunction "1_1") (pintype "passive"))
      (node (ref "R54") (pin "2") (pinfunction "2_2") (pintype "passive"))
      (node (ref "R55") (pin "2") (pinfunction "2_2") (pintype "passive"))
      (node (ref "R56") (pin "2") (pinfunction "2_2") (pintype "passive"))
      (node (ref "R57") (pin "2") (pinfunction "2_2") (pintype "passive"))
      (node (ref "R58") (pin "2") (pinfunction "2_2") (pintype "passive"))
      (node (ref "U29") (pin "B3") (pinfunction "VIN1_B3") (pintype "passive"))
      (node (ref "U29") (pin "B4") (pinfunction "VIN1_B4") (pintype "passive"))
      (node (ref "U29") (pin "B5") (pinfunction "SVIN1_B5") (pintype "passive"))
      (node (ref "U29") (pin "E3") (pinfunction "VIN2_E3") (pintype "passive"))
      (node (ref "U29") (pin "E4") (pinfunction "VIN2_E4") (pintype "passive"))
      (node (ref "U29") (pin "E5") (pinfunction "SVIN2_E5") (pintype "passive"))
      (node (ref "U29") (pin "H3") (pinfunction "VIN3_H3") (pintype "passive"))
      (node (ref "U29") (pin "H4") (pinfunction "VIN3_H4") (pintype "passive"))
      (node (ref "U29") (pin "H5") (pinfunction "SVIN3_H5") (pintype "passive"))
      (node (ref "U29") (pin "L3") (pinfunction "VIN4_L3") (pintype "passive"))
      (node (ref "U29") (pin "L4") (pinfunction "VIN4_L4") (pintype "passive"))
      (node (ref "U29") (pin "L5") (pinfunction "SVIN4_L5") (pintype "passive"))
    )
    (net (code "26") (name "/Vout-I1") (class "Default")
      (node (ref "C11") (pin "1") (pinfunction "1_1") (pintype "passive"))
      (node (ref "C12") (pin "1") (pinfunction "1_1") (pintype "passive"))
      (node (ref "C13") (pin "1") (pinfunction "1_1") (pintype "passive"))
      (node (ref "C25") (pin "1") (pinfunction "1_1") (pintype "passive"))
      (node (ref "J1") (pin "1") (pinfunction "1_1") (pintype "passive"))
      (node (ref "J2") (pin "1") (pinfunction "1_1") (pintype "passive"))
      (node (ref "U29") (pin "A1") (pinfunction "VOUT1_A1") (pintype "passive"))
      (node (ref "U29") (pin "A2") (pinfunction "VOUT1_A2") (pintype "passive"))
      (node (ref "U29") (pin "A3") (pinfunction "VOUT1_A3") (pintype "passive"))
    )
    (net (code "27") (name "/Vout-I2") (class "Default")
      (node (ref "C14") (pin "1") (pinfunction "1_1") (pintype "passive"))
      (node (ref "C15") (pin "1") (pinfunction "1_1") (pintype "passive"))
      (node (ref "C16") (pin "1") (pinfunction "1_1") (pintype "passive"))
      (node (ref "C39") (pin "1") (pinfunction "1_1") (pintype "passive"))
      (node (ref "J5") (pin "1") (pinfunction "1_1") (pintype "passive"))
      (node (ref "J6") (pin "1") (pinfunction "1_1") (pintype "passive"))
      (node (ref "U29") (pin "C1") (pinfunction "VOUT2_C1") (pintype "passive"))
      (node (ref "U29") (pin "D1") (pinfunction "VOUT2_D1") (pintype "passive"))
      (node (ref "U29") (pin "D2") (pinfunction "VOUT2_D2") (pintype "passive"))
    )
    (net (code "28") (name "/Vout-I3") (class "Default")
      (node (ref "C18") (pin "1") (pinfunction "1_1") (pintype "passive"))
      (node (ref "C19") (pin "1") (pinfunction "1_1") (pintype "passive"))
      (node (ref "C20") (pin "1") (pinfunction "1_1") (pintype "passive"))
      (node (ref "C41") (pin "1") (pinfunction "1_1") (pintype "passive"))
      (node (ref "J7") (pin "1") (pinfunction "1_1") (pintype "passive"))
      (node (ref "J8") (pin "1") (pinfunction "1_1") (pintype "passive"))
      (node (ref "U29") (pin "F1") (pinfunction "VOUT3_F1") (pintype "passive"))
      (node (ref "U29") (pin "G1") (pinfunction "VOUT3_G1") (pintype "passive"))
      (node (ref "U29") (pin "G2") (pinfunction "VOUT3_G2") (pintype "passive"))
    )
    (net (code "29") (name "/Vout-I4") (class "Default")
      (node (ref "C21") (pin "1") (pinfunction "1_1") (pintype "passive"))
      (node (ref "C22") (pin "1") (pinfunction "1_1") (pintype "passive"))
      (node (ref "C23") (pin "1") (pinfunction "1_1") (pintype "passive"))
      (node (ref "C43") (pin "1") (pinfunction "1_1") (pintype "passive"))
      (node (ref "J10") (pin "1") (pinfunction "1_1") (pintype "passive"))
      (node (ref "J9") (pin "1") (pinfunction "1_1") (pintype "passive"))
      (node (ref "U29") (pin "J1") (pinfunction "VOUT4_J1") (pintype "passive"))
      (node (ref "U29") (pin "K1") (pinfunction "VOUT4_K1") (pintype "passive"))
      (node (ref "U29") (pin "K2") (pinfunction "VOUT4_K2") (pintype "passive"))
    )
    (net (code "30") (name "/Vout1") (class "Default")
      (node (ref "J1") (pin "2") (pinfunction "2_2") (pintype "passive"))
      (node (ref "J2") (pin "2") (pinfunction "2_2") (pintype "passive"))
    )
    (net (code "31") (name "/Vout2") (class "Default")
      (node (ref "J5") (pin "2") (pinfunction "2_2") (pintype "passive"))
      (node (ref "J6") (pin "2") (pinfunction "2_2") (pintype "passive"))
    )
    (net (code "32") (name "/Vout3") (class "Default")
      (node (ref "J7") (pin "2") (pinfunction "2_2") (pintype "passive"))
      (node (ref "J8") (pin "2") (pinfunction "2_2") (pintype "passive"))
    )
    (net (code "33") (name "/Vout4") (class "Default")
      (node (ref "J10") (pin "2") (pinfunction "2_2") (pintype "passive"))
      (node (ref "J9") (pin "2") (pinfunction "2_2") (pintype "passive"))
    )
    (net (code "34") (name "5V0") (class "Default")
      (node (ref "R94") (pin "2") (pinfunction "2_2") (pintype "passive"))
      (node (ref "R95") (pin "2") (pinfunction "2_2") (pintype "passive"))
      (node (ref "R96") (pin "2") (pinfunction "2_2") (pintype "passive"))
      (node (ref "R97") (pin "2") (pinfunction "2_2") (pintype "passive"))
    )
    (net (code "35") (name "GND") (class "Default")
      (node (ref "C1") (pin "2") (pinfunction "2_2") (pintype "passive"))
      (node (ref "C11") (pin "2") (pinfunction "2_2") (pintype "passive"))
      (node (ref "C12") (pin "2") (pinfunction "2_2") (pintype "passive"))
      (node (ref "C13") (pin "2") (pinfunction "2_2") (pintype "passive"))
      (node (ref "C14") (pin "2") (pinfunction "2_2") (pintype "passive"))
      (node (ref "C15") (pin "2") (pinfunction "2_2") (pintype "passive"))
      (node (ref "C16") (pin "2") (pinfunction "2_2") (pintype "passive"))
      (node (ref "C18") (pin "2") (pinfunction "2_2") (pintype "passive"))
      (node (ref "C19") (pin "2") (pinfunction "2_2") (pintype "passive"))
      (node (ref "C2") (pin "2") (pinfunction "2_2") (pintype "passive"))
      (node (ref "C20") (pin "2") (pinfunction "2_2") (pintype "passive"))
      (node (ref "C21") (pin "2") (pinfunction "2_2") (pintype "passive"))
      (node (ref "C22") (pin "2") (pinfunction "2_2") (pintype "passive"))
      (node (ref "C23") (pin "2") (pinfunction "2_2") (pintype "passive"))
      (node (ref "C24") (pin "2") (pinfunction "2_2") (pintype "passive"))
      (node (ref "C26") (pin "2") (pinfunction "2_2") (pintype "passive"))
      (node (ref "C27") (pin "2") (pinfunction "2_2") (pintype "passive"))
      (node (ref "C28") (pin "2") (pinfunction "2_2") (pintype "passive"))
      (node (ref "C29") (pin "2") (pinfunction "2_2") (pintype "passive"))
      (node (ref "C3") (pin "2") (pinfunction "2_2") (pintype "passive"))
      (node (ref "C30") (pin "2") (pinfunction "2_2") (pintype "passive"))
      (node (ref "C31") (pin "2") (pinfunction "2_2") (pintype "passive"))
      (node (ref "C32") (pin "2") (pinfunction "2_2") (pintype "passive"))
      (node (ref "C33") (pin "2") (pinfunction "2_2") (pintype "passive"))
      (node (ref "C34") (pin "2") (pinfunction "2_2") (pintype "passive"))
      (node (ref "C35") (pin "2") (pinfunction "2_2") (pintype "passive"))
      (node (ref "C36") (pin "2") (pinfunction "2_2") (pintype "passive"))
      (node (ref "C37") (pin "2") (pinfunction "2_2") (pintype "passive"))
      (node (ref "C38") (pin "2") (pinfunction "2_2") (pintype "passive"))
      (node (ref "C4") (pin "2") (pinfunction "2_2") (pintype "passive"))
      (node (ref "C40") (pin "2") (pinfunction "2_2") (pintype "passive"))
      (node (ref "C42") (pin "2") (pinfunction "2_2") (pintype "passive"))
      (node (ref "C5") (pin "2") (pinfunction "2_2") (pintype "passive"))
      (node (ref "C6") (pin "2") (pinfunction "2_2") (pintype "passive"))
      (node (ref "C7") (pin "2") (pinfunction "2_2") (pintype "passive"))
      (node (ref "C8") (pin "2") (pinfunction "2_2") (pintype "passive"))
      (node (ref "R67") (pin "1") (pinfunction "1_1") (pintype "passive"))
      (node (ref "R68") (pin "1") (pinfunction "1_1") (pintype "passive"))
      (node (ref "R69") (pin "1") (pinfunction "1_1") (pintype "passive"))
      (node (ref "R70") (pin "1") (pinfunction "1_1") (pintype "passive"))
      (node (ref "R71") (pin "1") (pinfunction "1_1") (pintype "passive"))
      (node (ref "R72") (pin "1") (pinfunction "1_1") (pintype "passive"))
      (node (ref "R73") (pin "1") (pinfunction "1_1") (pintype "passive"))
      (node (ref "R74") (pin "1") (pinfunction "1_1") (pintype "passive"))
      (node (ref "R75") (pin "1") (pinfunction "1_1") (pintype "passive"))
      (node (ref "R76") (pin "1") (pinfunction "1_1") (pintype "passive"))
      (node (ref "R77") (pin "1") (pinfunction "1_1") (pintype "passive"))
      (node (ref "R78") (pin "1") (pinfunction "1_1") (pintype "passive"))
      (node (ref "U29") (pin "A4") (pinfunction "GND_A4") (pintype "passive"))
      (node (ref "U29") (pin "A5") (pinfunction "GND_A5") (pintype "passive"))
      (node (ref "U29") (pin "B1") (pinfunction "GND_B1") (pintype "passive"))
      (node (ref "U29") (pin "B2") (pinfunction "GND_B2") (pintype "passive"))
      (node (ref "U29") (pin "C5") (pinfunction "GND_C5") (pintype "passive"))
      (node (ref "U29") (pin "D3") (pinfunction "GND_D3") (pintype "passive"))
      (node (ref "U29") (pin "D4") (pinfunction "GND_D4") (pintype "passive"))
      (node (ref "U29") (pin "D5") (pinfunction "GND_D5") (pintype "passive"))
      (node (ref "U29") (pin "E1") (pinfunction "GND_E1") (pintype "passive"))
      (node (ref "U29") (pin "E2") (pinfunction "GND_E2") (pintype "passive"))
      (node (ref "U29") (pin "F5") (pinfunction "GND_F5") (pintype "passive"))
      (node (ref "U29") (pin "F7") (pinfunction "SGND_F7") (pintype "passive"))
      (node (ref "U29") (pin "G3") (pinfunction "GND_G3") (pintype "passive"))
      (node (ref "U29") (pin "G4") (pinfunction "GND_G4") (pintype "passive"))
      (node (ref "U29") (pin "G5") (pinfunction "GND_G5") (pintype "passive"))
      (node (ref "U29") (pin "H1") (pinfunction "GND_H1") (pintype "passive"))
      (node (ref "U29") (pin "H2") (pinfunction "GND_H2") (pintype "passive"))
      (node (ref "U29") (pin "J5") (pinfunction "GND_J5") (pintype "passive"))
      (node (ref "U29") (pin "K3") (pinfunction "GND_K3") (pintype "passive"))
      (node (ref "U29") (pin "K4") (pinfunction "GND_K4") (pintype "passive"))
      (node (ref "U29") (pin "L1") (pinfunction "GND_L1") (pintype "passive"))
      (node (ref "U29") (pin "L2") (pinfunction "GND_L2") (pintype "passive"))
    )
    (net (code "36") (name "Net-(C27-Pad1)") (class "Default")
      (node (ref "C27") (pin "1") (pinfunction "1_1") (pintype "passive"))
      (node (ref "R64") (pin "1") (pinfunction "1_1") (pintype "passive"))
    )
    (net (code "37") (name "Net-(C30-Pad1)") (class "Default")
      (node (ref "C30") (pin "1") (pinfunction "1_1") (pintype "passive"))
      (node (ref "R65") (pin "1") (pinfunction "1_1") (pintype "passive"))
    )
    (net (code "38") (name "Net-(C33-Pad1)") (class "Default")
      (node (ref "C33") (pin "1") (pinfunction "1_1") (pintype "passive"))
      (node (ref "R63") (pin "1") (pinfunction "1_1") (pintype "passive"))
    )
    (net (code "39") (name "Net-(C36-Pad1)") (class "Default")
      (node (ref "C36") (pin "1") (pinfunction "1_1") (pintype "passive"))
      (node (ref "R66") (pin "1") (pinfunction "1_1") (pintype "passive"))
    )
    (net (code "40") (name "Net-(D9-Anode)") (class "Default")
      (node (ref "D9") (pin "1") (pinfunction "Anode_1") (pintype "passive"))
      (node (ref "R94") (pin "1") (pinfunction "1_1") (pintype "passive"))
    )
    (net (code "41") (name "Net-(D10-Anode)") (class "Default")
      (node (ref "D10") (pin "1") (pinfunction "Anode_1") (pintype "passive"))
      (node (ref "R95") (pin "1") (pinfunction "1_1") (pintype "passive"))
    )
    (net (code "42") (name "Net-(D11-Anode)") (class "Default")
      (node (ref "D11") (pin "1") (pinfunction "Anode_1") (pintype "passive"))
      (node (ref "R96") (pin "1") (pinfunction "1_1") (pintype "passive"))
    )
    (net (code "43") (name "Net-(D12-Anode)") (class "Default")
      (node (ref "D12") (pin "1") (pinfunction "Anode_1") (pintype "passive"))
      (node (ref "R97") (pin "1") (pinfunction "1_1") (pintype "passive"))
    )
    (net (code "44") (name "Net-(U29-MODE1)") (class "Default")
      (node (ref "R59") (pin "1") (pinfunction "1_1") (pintype "passive"))
      (node (ref "R77") (pin "2") (pinfunction "2_2") (pintype "passive"))
      (node (ref "U29") (pin "B6") (pinfunction "MODE1_B6") (pintype "passive"))
    )
    (net (code "45") (name "Net-(U29-MODE2)") (class "Default")
      (node (ref "R60") (pin "1") (pinfunction "1_1") (pintype "passive"))
      (node (ref "R74") (pin "2") (pinfunction "2_2") (pintype "passive"))
      (node (ref "U29") (pin "E6") (pinfunction "MODE2_E6") (pintype "passive"))
    )
    (net (code "46") (name "Net-(U29-MODE3)") (class "Default")
      (node (ref "R61") (pin "1") (pinfunction "1_1") (pintype "passive"))
      (node (ref "R71") (pin "2") (pinfunction "2_2") (pintype "passive"))
      (node (ref "U29") (pin "H6") (pinfunction "MODE3_H6") (pintype "passive"))
    )
    (net (code "47") (name "Net-(U29-MODE4)") (class "Default")
      (node (ref "R62") (pin "1") (pinfunction "1_1") (pintype "passive"))
      (node (ref "R68") (pin "2") (pinfunction "2_2") (pintype "passive"))
      (node (ref "U29") (pin "L6") (pinfunction "MODE4_L6") (pintype "passive"))
    )
    (net (code "48") (name "Net-(U29-TEMP)") (class "Default")
      (node (ref "R58") (pin "1") (pinfunction "1_1") (pintype "passive"))
      (node (ref "U29") (pin "F3") (pinfunction "TEMP_F3") (pintype "passive"))
    )
    (net (code "49") (name "unconnected-(U29-CLKIN-PadC7)") (class "Default")
      (node (ref "U29") (pin "C7") (pinfunction "CLKIN_C7") (pintype "passive+no_connect"))
    )
    (net (code "50") (name "unconnected-(U29-CLKOUT-PadJ3)") (class "Default")
      (node (ref "U29") (pin "J3") (pinfunction "CLKOUT_J3") (pintype "passive+no_connect"))
    )
  )
)
